# Main_Board_Motor_Control.net
KiCad netlist of a schematic drawn in Altium Designer
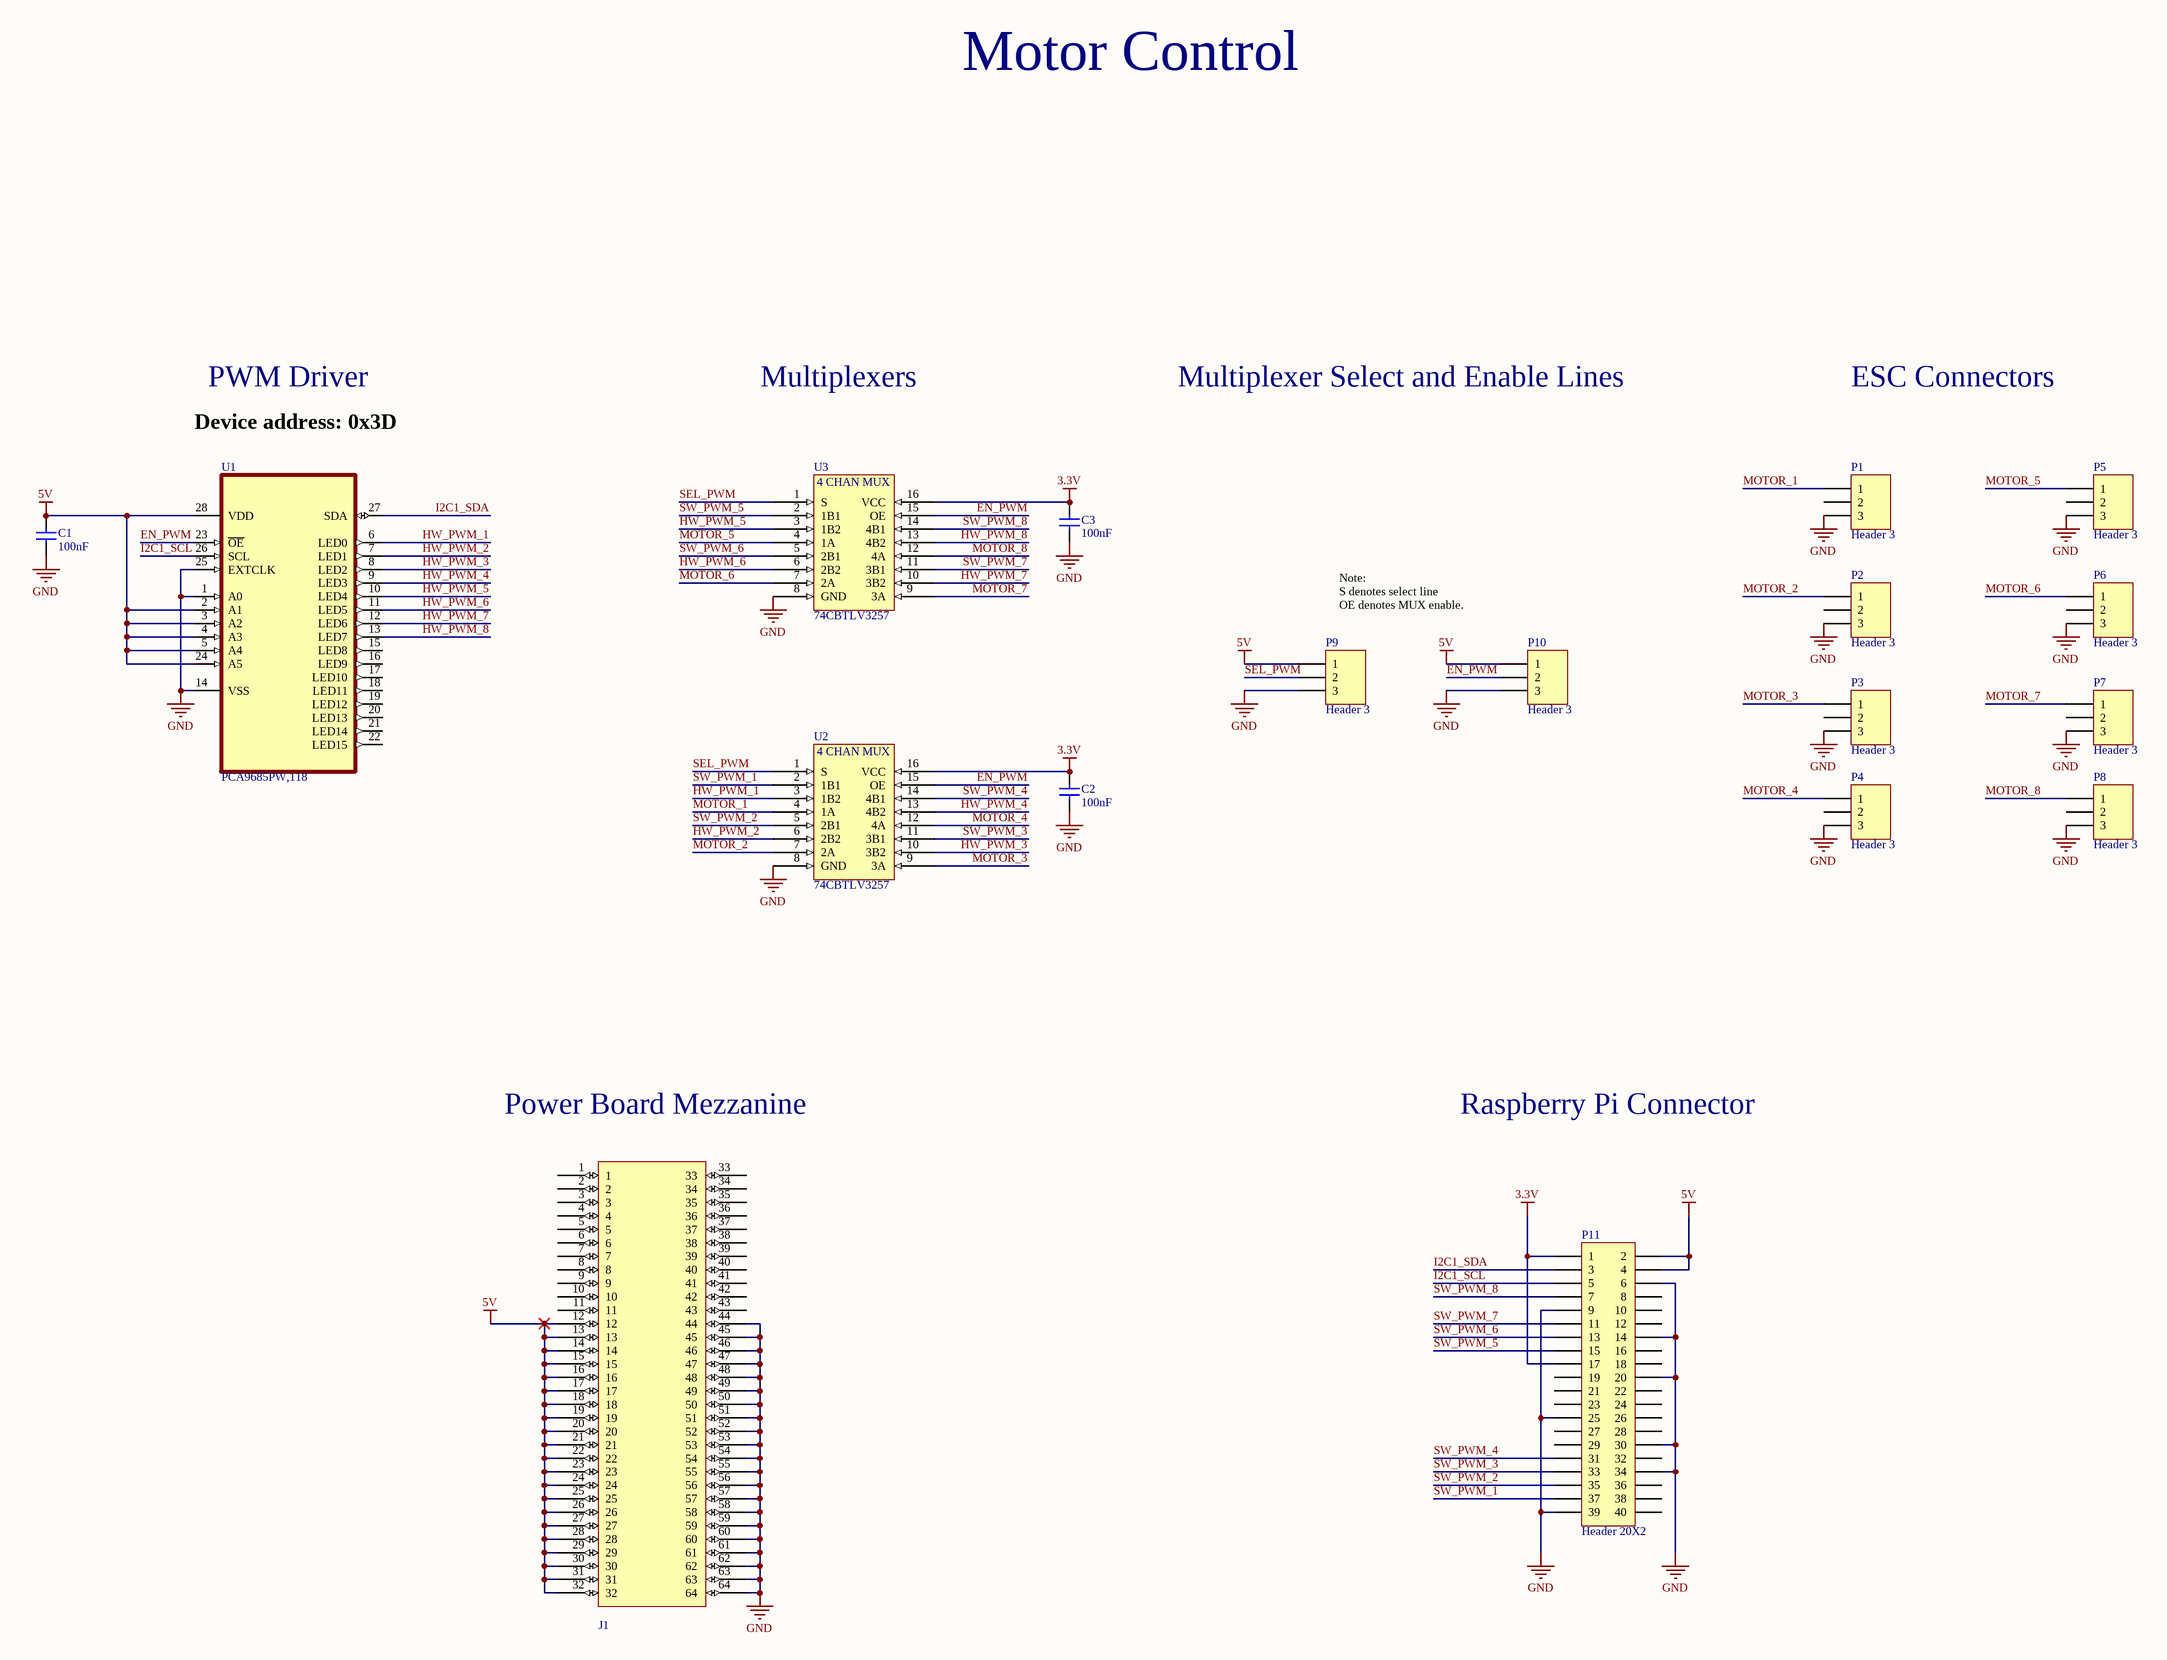
[diagram p0: Main Board Motor Control.SchDoc]

(export (version "E")
  (design (tool "Eeschema 10.0.6"))
  (components
    (comp (ref "C1")
      (value "100nF")
      (footprint "CAPC0603")
      (description "0.1 µF ±10% 50V Ceramic Capacitor X7R 0603 (1608 Metric)")
      (fields (field (name "Comment") "CL10B104KB8NNNC"))
      (libsource (lib "Passives") (part "CL10B104KB8NNNC"))
    )
    (comp (ref "C2")
      (value "100nF")
      (footprint "CAPC0603")
      (description "0.1 µF ±10% 50V Ceramic Capacitor X7R 0603 (1608 Metric)")
      (fields (field (name "Comment") "CL10B104KB8NNNC"))
      (libsource (lib "Passives") (part "CL10B104KB8NNNC"))
    )
    (comp (ref "C3")
      (value "100nF")
      (footprint "CAPC0603")
      (description "0.1 µF ±10% 50V Ceramic Capacitor X7R 0603 (1608 Metric)")
      (fields (field (name "Comment") "CL10B104KB8NNNC"))
      (libsource (lib "Passives") (part "CL10B104KB8NNNC"))
    )
    (comp (ref "J1")
      (value "0714362164")
      (footprint "1.0mm mezzanine connector 64 pin")
      (description "64 Position Connector Plug, Center Strip Contacts Surface Mount Gold")
      (libsource (lib "Connectors") (part "0714362164"))
    )
    (comp (ref "P1")
      (value "Header 3")
      (footprint "HDR1X3")
      (description "Header, 3-Pin")
      (fields (field (name "PUBLISHER") "Altium Limited"))
      (libsource (lib "Miscellaneous Connectors") (part "Header 3"))
    )
    (comp (ref "P2")
      (value "Header 3")
      (footprint "HDR1X3")
      (description "Header, 3-Pin")
      (fields (field (name "PUBLISHER") "Altium Limited"))
      (libsource (lib "Miscellaneous Connectors") (part "Header 3"))
    )
    (comp (ref "P3")
      (value "Header 3")
      (footprint "HDR1X3")
      (description "Header, 3-Pin")
      (fields (field (name "PUBLISHER") "Altium Limited"))
      (libsource (lib "Miscellaneous Connectors") (part "Header 3"))
    )
    (comp (ref "P4")
      (value "Header 3")
      (footprint "HDR1X3")
      (description "Header, 3-Pin")
      (fields (field (name "PUBLISHER") "Altium Limited"))
      (libsource (lib "Miscellaneous Connectors") (part "Header 3"))
    )
    (comp (ref "P5")
      (value "Header 3")
      (footprint "HDR1X3")
      (description "Header, 3-Pin")
      (fields (field (name "PUBLISHER") "Altium Limited"))
      (libsource (lib "Miscellaneous Connectors") (part "Header 3"))
    )
    (comp (ref "P6")
      (value "Header 3")
      (footprint "HDR1X3")
      (description "Header, 3-Pin")
      (fields (field (name "PUBLISHER") "Altium Limited"))
      (libsource (lib "Miscellaneous Connectors") (part "Header 3"))
    )
    (comp (ref "P7")
      (value "Header 3")
      (footprint "HDR1X3")
      (description "Header, 3-Pin")
      (fields (field (name "PUBLISHER") "Altium Limited"))
      (libsource (lib "Miscellaneous Connectors") (part "Header 3"))
    )
    (comp (ref "P8")
      (value "Header 3")
      (footprint "HDR1X3")
      (description "Header, 3-Pin")
      (fields (field (name "PUBLISHER") "Altium Limited"))
      (libsource (lib "Miscellaneous Connectors") (part "Header 3"))
    )
    (comp (ref "P9")
      (value "Header 3")
      (footprint "HDR1X3")
      (description "Header, 3-Pin")
      (fields (field (name "PUBLISHER") "Altium Limited"))
      (libsource (lib "Miscellaneous Connectors") (part "Header 3"))
    )
    (comp (ref "P10")
      (value "Header 3")
      (footprint "HDR1X3")
      (description "Header, 3-Pin")
      (fields (field (name "PUBLISHER") "Altium Limited"))
      (libsource (lib "Miscellaneous Connectors") (part "Header 3"))
    )
    (comp (ref "P11")
      (value "Header 20X2")
      (footprint "HDR2X20")
      (description "Header, 20-Pin, Dual row")
      (fields (field (name "PUBLISHER") "Altium Limited"))
      (libsource (lib "Miscellaneous Connectors") (part "Header 20X2"))
    )
    (comp (ref "U1")
      (value "PCA9685PW,118")
      (footprint "SOP65P640X110-28N")
      (description "LED Driver IC 16 Output Linear - PWM Dimming 25mA 28-TSSOP")
      (fields (field (name "MF") "NXP USA"))
      (libsource (lib "ICs") (part "PCA9685PW,118"))
    )
    (comp (ref "U2")
      (value "74CBTLV3257")
      (footprint "TSSOP16")
      (description "Mux; 4 channel; 2:1; Demux")
      (libsource (lib "ICs") (part "74CBTLV3257"))
    )
    (comp (ref "U3")
      (value "74CBTLV3257")
      (footprint "TSSOP16")
      (description "Mux; 4 channel; 2:1; Demux")
      (libsource (lib "ICs") (part "74CBTLV3257"))
    )
  )
  (nets
    (net (code "1") (name "/EN_PWM") (class "Default")
      (node (ref "P10") (pin "2") (pinfunction "2_2") (pintype "passive"))
      (node (ref "U1") (pin "23") (pinfunction "~{OE}_23") (pintype "input"))
      (node (ref "U2") (pin "15") (pinfunction "OE_15") (pintype "input"))
      (node (ref "U3") (pin "15") (pinfunction "OE_15") (pintype "input"))
    )
    (net (code "2") (name "/HW_PWM_1") (class "Default")
      (node (ref "U1") (pin "6") (pinfunction "LED0_6") (pintype "output"))
      (node (ref "U2") (pin "3") (pinfunction "1B2_3") (pintype "input"))
    )
    (net (code "3") (name "/HW_PWM_2") (class "Default")
      (node (ref "U1") (pin "7") (pinfunction "LED1_7") (pintype "output"))
      (node (ref "U2") (pin "6") (pinfunction "2B2_6") (pintype "input"))
    )
    (net (code "4") (name "/HW_PWM_3") (class "Default")
      (node (ref "U1") (pin "8") (pinfunction "LED2_8") (pintype "output"))
      (node (ref "U2") (pin "10") (pinfunction "3B2_10") (pintype "input"))
    )
    (net (code "5") (name "/HW_PWM_4") (class "Default")
      (node (ref "U1") (pin "9") (pinfunction "LED3_9") (pintype "output"))
      (node (ref "U2") (pin "13") (pinfunction "4B2_13") (pintype "input"))
    )
    (net (code "6") (name "/HW_PWM_5") (class "Default")
      (node (ref "U1") (pin "10") (pinfunction "LED4_10") (pintype "output"))
      (node (ref "U3") (pin "3") (pinfunction "1B2_3") (pintype "input"))
    )
    (net (code "7") (name "/HW_PWM_6") (class "Default")
      (node (ref "U1") (pin "11") (pinfunction "LED5_11") (pintype "output"))
      (node (ref "U3") (pin "6") (pinfunction "2B2_6") (pintype "input"))
    )
    (net (code "8") (name "/HW_PWM_7") (class "Default")
      (node (ref "U1") (pin "12") (pinfunction "LED6_12") (pintype "output"))
      (node (ref "U3") (pin "10") (pinfunction "3B2_10") (pintype "input"))
    )
    (net (code "9") (name "/HW_PWM_8") (class "Default")
      (node (ref "U1") (pin "13") (pinfunction "LED7_13") (pintype "output"))
      (node (ref "U3") (pin "13") (pinfunction "4B2_13") (pintype "input"))
    )
    (net (code "10") (name "/I2C1_SCL") (class "Default")
      (node (ref "P11") (pin "5") (pinfunction "5_5") (pintype "passive"))
      (node (ref "U1") (pin "26") (pinfunction "SCL_26") (pintype "input"))
    )
    (net (code "11") (name "/I2C1_SDA") (class "Default")
      (node (ref "P11") (pin "3") (pinfunction "3_3") (pintype "passive"))
      (node (ref "U1") (pin "27") (pinfunction "SDA_27") (pintype "bidirectional"))
    )
    (net (code "12") (name "/MOTOR_1") (class "Default")
      (node (ref "P1") (pin "1") (pinfunction "1_1") (pintype "passive"))
      (node (ref "U2") (pin "4") (pinfunction "1A_4") (pintype "input"))
    )
    (net (code "13") (name "/MOTOR_2") (class "Default")
      (node (ref "P2") (pin "1") (pinfunction "1_1") (pintype "passive"))
      (node (ref "U2") (pin "7") (pinfunction "2A_7") (pintype "input"))
    )
    (net (code "14") (name "/MOTOR_3") (class "Default")
      (node (ref "P3") (pin "1") (pinfunction "1_1") (pintype "passive"))
      (node (ref "U2") (pin "9") (pinfunction "3A_9") (pintype "input"))
    )
    (net (code "15") (name "/MOTOR_4") (class "Default")
      (node (ref "P4") (pin "1") (pinfunction "1_1") (pintype "passive"))
      (node (ref "U2") (pin "12") (pinfunction "4A_12") (pintype "input"))
    )
    (net (code "16") (name "/MOTOR_5") (class "Default")
      (node (ref "P5") (pin "1") (pinfunction "1_1") (pintype "passive"))
      (node (ref "U3") (pin "4") (pinfunction "1A_4") (pintype "input"))
    )
    (net (code "17") (name "/MOTOR_6") (class "Default")
      (node (ref "P6") (pin "1") (pinfunction "1_1") (pintype "passive"))
      (node (ref "U3") (pin "7") (pinfunction "2A_7") (pintype "input"))
    )
    (net (code "18") (name "/MOTOR_7") (class "Default")
      (node (ref "P7") (pin "1") (pinfunction "1_1") (pintype "passive"))
      (node (ref "U3") (pin "9") (pinfunction "3A_9") (pintype "input"))
    )
    (net (code "19") (name "/MOTOR_8") (class "Default")
      (node (ref "P8") (pin "1") (pinfunction "1_1") (pintype "passive"))
      (node (ref "U3") (pin "12") (pinfunction "4A_12") (pintype "input"))
    )
    (net (code "20") (name "/SEL_PWM") (class "Default")
      (node (ref "P9") (pin "2") (pinfunction "2_2") (pintype "passive"))
      (node (ref "U2") (pin "1") (pinfunction "S_1") (pintype "input"))
      (node (ref "U3") (pin "1") (pinfunction "S_1") (pintype "input"))
    )
    (net (code "21") (name "/SW_PWM_1") (class "Default")
      (node (ref "P11") (pin "37") (pinfunction "37_37") (pintype "passive"))
      (node (ref "U2") (pin "2") (pinfunction "1B1_2") (pintype "input"))
    )
    (net (code "22") (name "/SW_PWM_2") (class "Default")
      (node (ref "P11") (pin "35") (pinfunction "35_35") (pintype "passive"))
      (node (ref "U2") (pin "5") (pinfunction "2B1_5") (pintype "input"))
    )
    (net (code "23") (name "/SW_PWM_3") (class "Default")
      (node (ref "P11") (pin "33") (pinfunction "33_33") (pintype "passive"))
      (node (ref "U2") (pin "11") (pinfunction "3B1_11") (pintype "input"))
    )
    (net (code "24") (name "/SW_PWM_4") (class "Default")
      (node (ref "P11") (pin "31") (pinfunction "31_31") (pintype "passive"))
      (node (ref "U2") (pin "14") (pinfunction "4B1_14") (pintype "input"))
    )
    (net (code "25") (name "/SW_PWM_5") (class "Default")
      (node (ref "P11") (pin "15") (pinfunction "15_15") (pintype "passive"))
      (node (ref "U3") (pin "2") (pinfunction "1B1_2") (pintype "input"))
    )
    (net (code "26") (name "/SW_PWM_6") (class "Default")
      (node (ref "P11") (pin "13") (pinfunction "13_13") (pintype "passive"))
      (node (ref "U3") (pin "5") (pinfunction "2B1_5") (pintype "input"))
    )
    (net (code "27") (name "/SW_PWM_7") (class "Default")
      (node (ref "P11") (pin "11") (pinfunction "11_11") (pintype "passive"))
      (node (ref "U3") (pin "11") (pinfunction "3B1_11") (pintype "input"))
    )
    (net (code "28") (name "/SW_PWM_8") (class "Default")
      (node (ref "P11") (pin "7") (pinfunction "7_7") (pintype "passive"))
      (node (ref "U3") (pin "14") (pinfunction "4B1_14") (pintype "input"))
    )
    (net (code "29") (name "3.3V") (class "Default")
      (node (ref "C2") (pin "1") (pinfunction "A_1") (pintype "passive"))
      (node (ref "C3") (pin "1") (pinfunction "A_1") (pintype "passive"))
      (node (ref "P11") (pin "1") (pinfunction "1_1") (pintype "passive"))
      (node (ref "P11") (pin "17") (pinfunction "17_17") (pintype "passive"))
      (node (ref "U2") (pin "16") (pinfunction "VCC_16") (pintype "input"))
      (node (ref "U3") (pin "16") (pinfunction "VCC_16") (pintype "input"))
    )
    (net (code "30") (name "5V") (class "Default")
      (node (ref "C1") (pin "1") (pinfunction "A_1") (pintype "passive"))
      (node (ref "J1") (pin "12") (pinfunction "12_12") (pintype "bidirectional"))
      (node (ref "J1") (pin "13") (pinfunction "13_13") (pintype "bidirectional"))
      (node (ref "J1") (pin "14") (pinfunction "14_14") (pintype "bidirectional"))
      (node (ref "J1") (pin "15") (pinfunction "15_15") (pintype "bidirectional"))
      (node (ref "J1") (pin "16") (pinfunction "16_16") (pintype "bidirectional"))
      (node (ref "J1") (pin "17") (pinfunction "17_17") (pintype "bidirectional"))
      (node (ref "J1") (pin "18") (pinfunction "18_18") (pintype "bidirectional"))
      (node (ref "J1") (pin "19") (pinfunction "19_19") (pintype "bidirectional"))
      (node (ref "J1") (pin "20") (pinfunction "20_20") (pintype "bidirectional"))
      (node (ref "J1") (pin "21") (pinfunction "21_21") (pintype "bidirectional"))
      (node (ref "J1") (pin "22") (pinfunction "22_22") (pintype "bidirectional"))
      (node (ref "J1") (pin "23") (pinfunction "23_23") (pintype "bidirectional"))
      (node (ref "J1") (pin "24") (pinfunction "24_24") (pintype "bidirectional"))
      (node (ref "J1") (pin "25") (pinfunction "25_25") (pintype "bidirectional"))
      (node (ref "J1") (pin "26") (pinfunction "26_26") (pintype "bidirectional"))
      (node (ref "J1") (pin "27") (pinfunction "27_27") (pintype "bidirectional"))
      (node (ref "J1") (pin "28") (pinfunction "28_28") (pintype "bidirectional"))
      (node (ref "J1") (pin "29") (pinfunction "29_29") (pintype "bidirectional"))
      (node (ref "J1") (pin "30") (pinfunction "30_30") (pintype "bidirectional"))
      (node (ref "J1") (pin "31") (pinfunction "31_31") (pintype "bidirectional"))
      (node (ref "J1") (pin "32") (pinfunction "32_32") (pintype "bidirectional"))
      (node (ref "P10") (pin "1") (pinfunction "1_1") (pintype "passive"))
      (node (ref "P11") (pin "2") (pinfunction "2_2") (pintype "passive"))
      (node (ref "P11") (pin "4") (pinfunction "4_4") (pintype "passive"))
      (node (ref "P9") (pin "1") (pinfunction "1_1") (pintype "passive"))
      (node (ref "U1") (pin "2") (pinfunction "A1_2") (pintype "input"))
      (node (ref "U1") (pin "24") (pinfunction "A5_24") (pintype "input"))
      (node (ref "U1") (pin "28") (pinfunction "VDD_28") (pintype "power_in"))
      (node (ref "U1") (pin "3") (pinfunction "A2_3") (pintype "input"))
      (node (ref "U1") (pin "4") (pinfunction "A3_4") (pintype "input"))
      (node (ref "U1") (pin "5") (pinfunction "A4_5") (pintype "input"))
    )
    (net (code "31") (name "GND") (class "Default")
      (node (ref "C1") (pin "2") (pinfunction "B_2") (pintype "passive"))
      (node (ref "C2") (pin "2") (pinfunction "B_2") (pintype "passive"))
      (node (ref "C3") (pin "2") (pinfunction "B_2") (pintype "passive"))
      (node (ref "J1") (pin "44") (pinfunction "44_44") (pintype "bidirectional"))
      (node (ref "J1") (pin "45") (pinfunction "45_45") (pintype "bidirectional"))
      (node (ref "J1") (pin "46") (pinfunction "46_46") (pintype "bidirectional"))
      (node (ref "J1") (pin "47") (pinfunction "47_47") (pintype "bidirectional"))
      (node (ref "J1") (pin "48") (pinfunction "48_48") (pintype "bidirectional"))
      (node (ref "J1") (pin "49") (pinfunction "49_49") (pintype "bidirectional"))
      (node (ref "J1") (pin "50") (pinfunction "50_50") (pintype "bidirectional"))
      (node (ref "J1") (pin "51") (pinfunction "51_51") (pintype "bidirectional"))
      (node (ref "J1") (pin "52") (pinfunction "52_52") (pintype "bidirectional"))
      (node (ref "J1") (pin "53") (pinfunction "53_53") (pintype "bidirectional"))
      (node (ref "J1") (pin "54") (pinfunction "54_54") (pintype "bidirectional"))
      (node (ref "J1") (pin "55") (pinfunction "55_55") (pintype "bidirectional"))
      (node (ref "J1") (pin "56") (pinfunction "56_56") (pintype "bidirectional"))
      (node (ref "J1") (pin "57") (pinfunction "57_57") (pintype "bidirectional"))
      (node (ref "J1") (pin "58") (pinfunction "58_58") (pintype "bidirectional"))
      (node (ref "J1") (pin "59") (pinfunction "59_59") (pintype "bidirectional"))
      (node (ref "J1") (pin "60") (pinfunction "60_60") (pintype "bidirectional"))
      (node (ref "J1") (pin "61") (pinfunction "61_61") (pintype "bidirectional"))
      (node (ref "J1") (pin "62") (pinfunction "62_62") (pintype "bidirectional"))
      (node (ref "J1") (pin "63") (pinfunction "63_63") (pintype "bidirectional"))
      (node (ref "J1") (pin "64") (pinfunction "64_64") (pintype "bidirectional"))
      (node (ref "P1") (pin "3") (pinfunction "3_3") (pintype "passive"))
      (node (ref "P10") (pin "3") (pinfunction "3_3") (pintype "passive"))
      (node (ref "P11") (pin "14") (pinfunction "14_14") (pintype "passive"))
      (node (ref "P11") (pin "20") (pinfunction "20_20") (pintype "passive"))
      (node (ref "P11") (pin "25") (pinfunction "25_25") (pintype "passive"))
      (node (ref "P11") (pin "30") (pinfunction "30_30") (pintype "passive"))
      (node (ref "P11") (pin "34") (pinfunction "34_34") (pintype "passive"))
      (node (ref "P11") (pin "39") (pinfunction "39_39") (pintype "passive"))
      (node (ref "P11") (pin "6") (pinfunction "6_6") (pintype "passive"))
      (node (ref "P11") (pin "9") (pinfunction "9_9") (pintype "passive"))
      (node (ref "P2") (pin "3") (pinfunction "3_3") (pintype "passive"))
      (node (ref "P3") (pin "3") (pinfunction "3_3") (pintype "passive"))
      (node (ref "P4") (pin "3") (pinfunction "3_3") (pintype "passive"))
      (node (ref "P5") (pin "3") (pinfunction "3_3") (pintype "passive"))
      (node (ref "P6") (pin "3") (pinfunction "3_3") (pintype "passive"))
      (node (ref "P7") (pin "3") (pinfunction "3_3") (pintype "passive"))
      (node (ref "P8") (pin "3") (pinfunction "3_3") (pintype "passive"))
      (node (ref "P9") (pin "3") (pinfunction "3_3") (pintype "passive"))
      (node (ref "U1") (pin "1") (pinfunction "A0_1") (pintype "input"))
      (node (ref "U1") (pin "14") (pinfunction "VSS_14") (pintype "passive"))
      (node (ref "U1") (pin "25") (pinfunction "EXTCLK_25") (pintype "input"))
      (node (ref "U2") (pin "8") (pinfunction "GND_8") (pintype "input"))
      (node (ref "U3") (pin "8") (pinfunction "GND_8") (pintype "input"))
    )
    (net (code "32") (name "unconnected-(J1-Pad1)") (class "Default")
      (node (ref "J1") (pin "1") (pinfunction "1_1") (pintype "bidirectional"))
    )
    (net (code "33") (name "unconnected-(J1-Pad2)") (class "Default")
      (node (ref "J1") (pin "2") (pinfunction "2_2") (pintype "bidirectional"))
    )
    (net (code "34") (name "unconnected-(J1-Pad3)") (class "Default")
      (node (ref "J1") (pin "3") (pinfunction "3_3") (pintype "bidirectional"))
    )
    (net (code "35") (name "unconnected-(J1-Pad4)") (class "Default")
      (node (ref "J1") (pin "4") (pinfunction "4_4") (pintype "bidirectional"))
    )
    (net (code "36") (name "unconnected-(J1-Pad5)") (class "Default")
      (node (ref "J1") (pin "5") (pinfunction "5_5") (pintype "bidirectional"))
    )
    (net (code "37") (name "unconnected-(J1-Pad6)") (class "Default")
      (node (ref "J1") (pin "6") (pinfunction "6_6") (pintype "bidirectional"))
    )
    (net (code "38") (name "unconnected-(J1-Pad7)") (class "Default")
      (node (ref "J1") (pin "7") (pinfunction "7_7") (pintype "bidirectional"))
    )
    (net (code "39") (name "unconnected-(J1-Pad8)") (class "Default")
      (node (ref "J1") (pin "8") (pinfunction "8_8") (pintype "bidirectional"))
    )
    (net (code "40") (name "unconnected-(J1-Pad9)") (class "Default")
      (node (ref "J1") (pin "9") (pinfunction "9_9") (pintype "bidirectional"))
    )
    (net (code "41") (name "unconnected-(J1-Pad10)") (class "Default")
      (node (ref "J1") (pin "10") (pinfunction "10_10") (pintype "bidirectional"))
    )
    (net (code "42") (name "unconnected-(J1-Pad11)") (class "Default")
      (node (ref "J1") (pin "11") (pinfunction "11_11") (pintype "bidirectional"))
    )
    (net (code "43") (name "unconnected-(J1-Pad33)") (class "Default")
      (node (ref "J1") (pin "33") (pinfunction "33_33") (pintype "bidirectional"))
    )
    (net (code "44") (name "unconnected-(J1-Pad34)") (class "Default")
      (node (ref "J1") (pin "34") (pinfunction "34_34") (pintype "bidirectional"))
    )
    (net (code "45") (name "unconnected-(J1-Pad35)") (class "Default")
      (node (ref "J1") (pin "35") (pinfunction "35_35") (pintype "bidirectional"))
    )
    (net (code "46") (name "unconnected-(J1-Pad36)") (class "Default")
      (node (ref "J1") (pin "36") (pinfunction "36_36") (pintype "bidirectional"))
    )
    (net (code "47") (name "unconnected-(J1-Pad37)") (class "Default")
      (node (ref "J1") (pin "37") (pinfunction "37_37") (pintype "bidirectional"))
    )
    (net (code "48") (name "unconnected-(J1-Pad38)") (class "Default")
      (node (ref "J1") (pin "38") (pinfunction "38_38") (pintype "bidirectional"))
    )
    (net (code "49") (name "unconnected-(J1-Pad39)") (class "Default")
      (node (ref "J1") (pin "39") (pinfunction "39_39") (pintype "bidirectional"))
    )
    (net (code "50") (name "unconnected-(J1-Pad40)") (class "Default")
      (node (ref "J1") (pin "40") (pinfunction "40_40") (pintype "bidirectional"))
    )
    (net (code "51") (name "unconnected-(J1-Pad41)") (class "Default")
      (node (ref "J1") (pin "41") (pinfunction "41_41") (pintype "bidirectional"))
    )
    (net (code "52") (name "unconnected-(J1-Pad42)") (class "Default")
      (node (ref "J1") (pin "42") (pinfunction "42_42") (pintype "bidirectional"))
    )
    (net (code "53") (name "unconnected-(J1-Pad43)") (class "Default")
      (node (ref "J1") (pin "43") (pinfunction "43_43") (pintype "bidirectional"))
    )
    (net (code "54") (name "unconnected-(P1-Pad2)") (class "Default")
      (node (ref "P1") (pin "2") (pinfunction "2_2") (pintype "passive"))
    )
    (net (code "55") (name "unconnected-(P2-Pad2)") (class "Default")
      (node (ref "P2") (pin "2") (pinfunction "2_2") (pintype "passive"))
    )
    (net (code "56") (name "unconnected-(P3-Pad2)") (class "Default")
      (node (ref "P3") (pin "2") (pinfunction "2_2") (pintype "passive"))
    )
    (net (code "57") (name "unconnected-(P4-Pad2)") (class "Default")
      (node (ref "P4") (pin "2") (pinfunction "2_2") (pintype "passive"))
    )
    (net (code "58") (name "unconnected-(P5-Pad2)") (class "Default")
      (node (ref "P5") (pin "2") (pinfunction "2_2") (pintype "passive"))
    )
    (net (code "59") (name "unconnected-(P6-Pad2)") (class "Default")
      (node (ref "P6") (pin "2") (pinfunction "2_2") (pintype "passive"))
    )
    (net (code "60") (name "unconnected-(P7-Pad2)") (class "Default")
      (node (ref "P7") (pin "2") (pinfunction "2_2") (pintype "passive"))
    )
    (net (code "61") (name "unconnected-(P8-Pad2)") (class "Default")
      (node (ref "P8") (pin "2") (pinfunction "2_2") (pintype "passive"))
    )
    (net (code "62") (name "unconnected-(P11-Pad8)") (class "Default")
      (node (ref "P11") (pin "8") (pinfunction "8_8") (pintype "passive"))
    )
    (net (code "63") (name "unconnected-(P11-Pad10)") (class "Default")
      (node (ref "P11") (pin "10") (pinfunction "10_10") (pintype "passive"))
    )
    (net (code "64") (name "unconnected-(P11-Pad12)") (class "Default")
      (node (ref "P11") (pin "12") (pinfunction "12_12") (pintype "passive"))
    )
    (net (code "65") (name "unconnected-(P11-Pad16)") (class "Default")
      (node (ref "P11") (pin "16") (pinfunction "16_16") (pintype "passive"))
    )
    (net (code "66") (name "unconnected-(P11-Pad18)") (class "Default")
      (node (ref "P11") (pin "18") (pinfunction "18_18") (pintype "passive"))
    )
    (net (code "67") (name "unconnected-(P11-Pad19)") (class "Default")
      (node (ref "P11") (pin "19") (pinfunction "19_19") (pintype "passive"))
    )
    (net (code "68") (name "unconnected-(P11-Pad21)") (class "Default")
      (node (ref "P11") (pin "21") (pinfunction "21_21") (pintype "passive"))
    )
    (net (code "69") (name "unconnected-(P11-Pad22)") (class "Default")
      (node (ref "P11") (pin "22") (pinfunction "22_22") (pintype "passive"))
    )
    (net (code "70") (name "unconnected-(P11-Pad23)") (class "Default")
      (node (ref "P11") (pin "23") (pinfunction "23_23") (pintype "passive"))
    )
    (net (code "71") (name "unconnected-(P11-Pad24)") (class "Default")
      (node (ref "P11") (pin "24") (pinfunction "24_24") (pintype "passive"))
    )
    (net (code "72") (name "unconnected-(P11-Pad26)") (class "Default")
      (node (ref "P11") (pin "26") (pinfunction "26_26") (pintype "passive"))
    )
    (net (code "73") (name "unconnected-(P11-Pad27)") (class "Default")
      (node (ref "P11") (pin "27") (pinfunction "27_27") (pintype "passive"))
    )
    (net (code "74") (name "unconnected-(P11-Pad28)") (class "Default")
      (node (ref "P11") (pin "28") (pinfunction "28_28") (pintype "passive"))
    )
    (net (code "75") (name "unconnected-(P11-Pad29)") (class "Default")
      (node (ref "P11") (pin "29") (pinfunction "29_29") (pintype "passive"))
    )
    (net (code "76") (name "unconnected-(P11-Pad32)") (class "Default")
      (node (ref "P11") (pin "32") (pinfunction "32_32") (pintype "passive"))
    )
    (net (code "77") (name "unconnected-(P11-Pad36)") (class "Default")
      (node (ref "P11") (pin "36") (pinfunction "36_36") (pintype "passive"))
    )
    (net (code "78") (name "unconnected-(P11-Pad38)") (class "Default")
      (node (ref "P11") (pin "38") (pinfunction "38_38") (pintype "passive"))
    )
    (net (code "79") (name "unconnected-(P11-Pad40)") (class "Default")
      (node (ref "P11") (pin "40") (pinfunction "40_40") (pintype "passive"))
    )
    (net (code "80") (name "unconnected-(U1-LED8-Pad15)") (class "Default")
      (node (ref "U1") (pin "15") (pinfunction "LED8_15") (pintype "output"))
    )
    (net (code "81") (name "unconnected-(U1-LED9-Pad16)") (class "Default")
      (node (ref "U1") (pin "16") (pinfunction "LED9_16") (pintype "output"))
    )
    (net (code "82") (name "unconnected-(U1-LED10-Pad17)") (class "Default")
      (node (ref "U1") (pin "17") (pinfunction "LED10_17") (pintype "output"))
    )
    (net (code "83") (name "unconnected-(U1-LED11-Pad18)") (class "Default")
      (node (ref "U1") (pin "18") (pinfunction "LED11_18") (pintype "output"))
    )
    (net (code "84") (name "unconnected-(U1-LED12-Pad19)") (class "Default")
      (node (ref "U1") (pin "19") (pinfunction "LED12_19") (pintype "output"))
    )
    (net (code "85") (name "unconnected-(U1-LED13-Pad20)") (class "Default")
      (node (ref "U1") (pin "20") (pinfunction "LED13_20") (pintype "output"))
    )
    (net (code "86") (name "unconnected-(U1-LED14-Pad21)") (class "Default")
      (node (ref "U1") (pin "21") (pinfunction "LED14_21") (pintype "output"))
    )
    (net (code "87") (name "unconnected-(U1-LED15-Pad22)") (class "Default")
      (node (ref "U1") (pin "22") (pinfunction "LED15_22") (pintype "output"))
    )
  )
)
